# Schematic_MC.net
KiCad netlist of a schematic drawn in Altium Designer
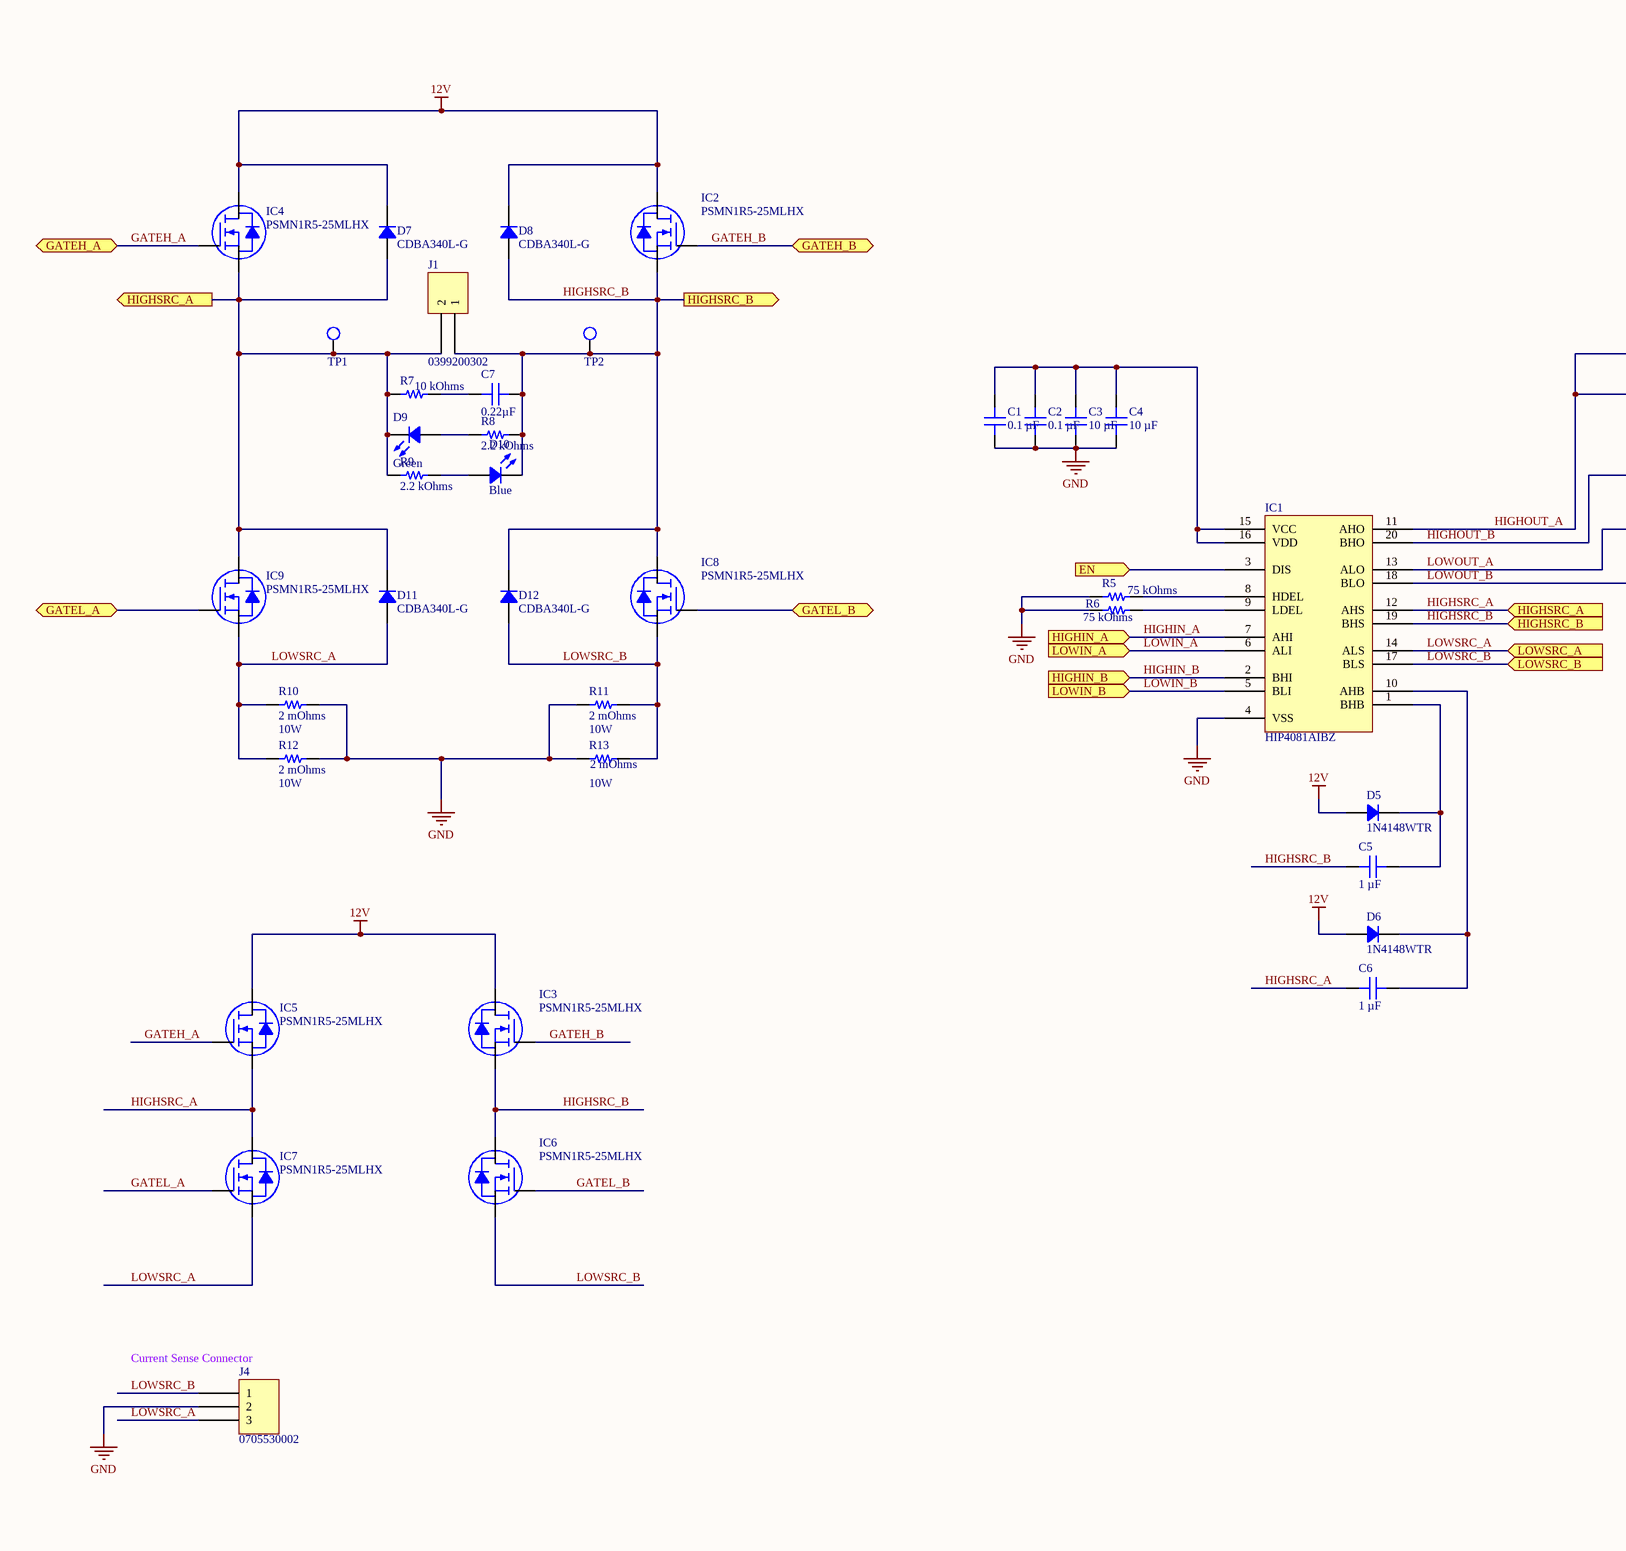
[diagram p0: Schematic_MC.SchDoc, left]
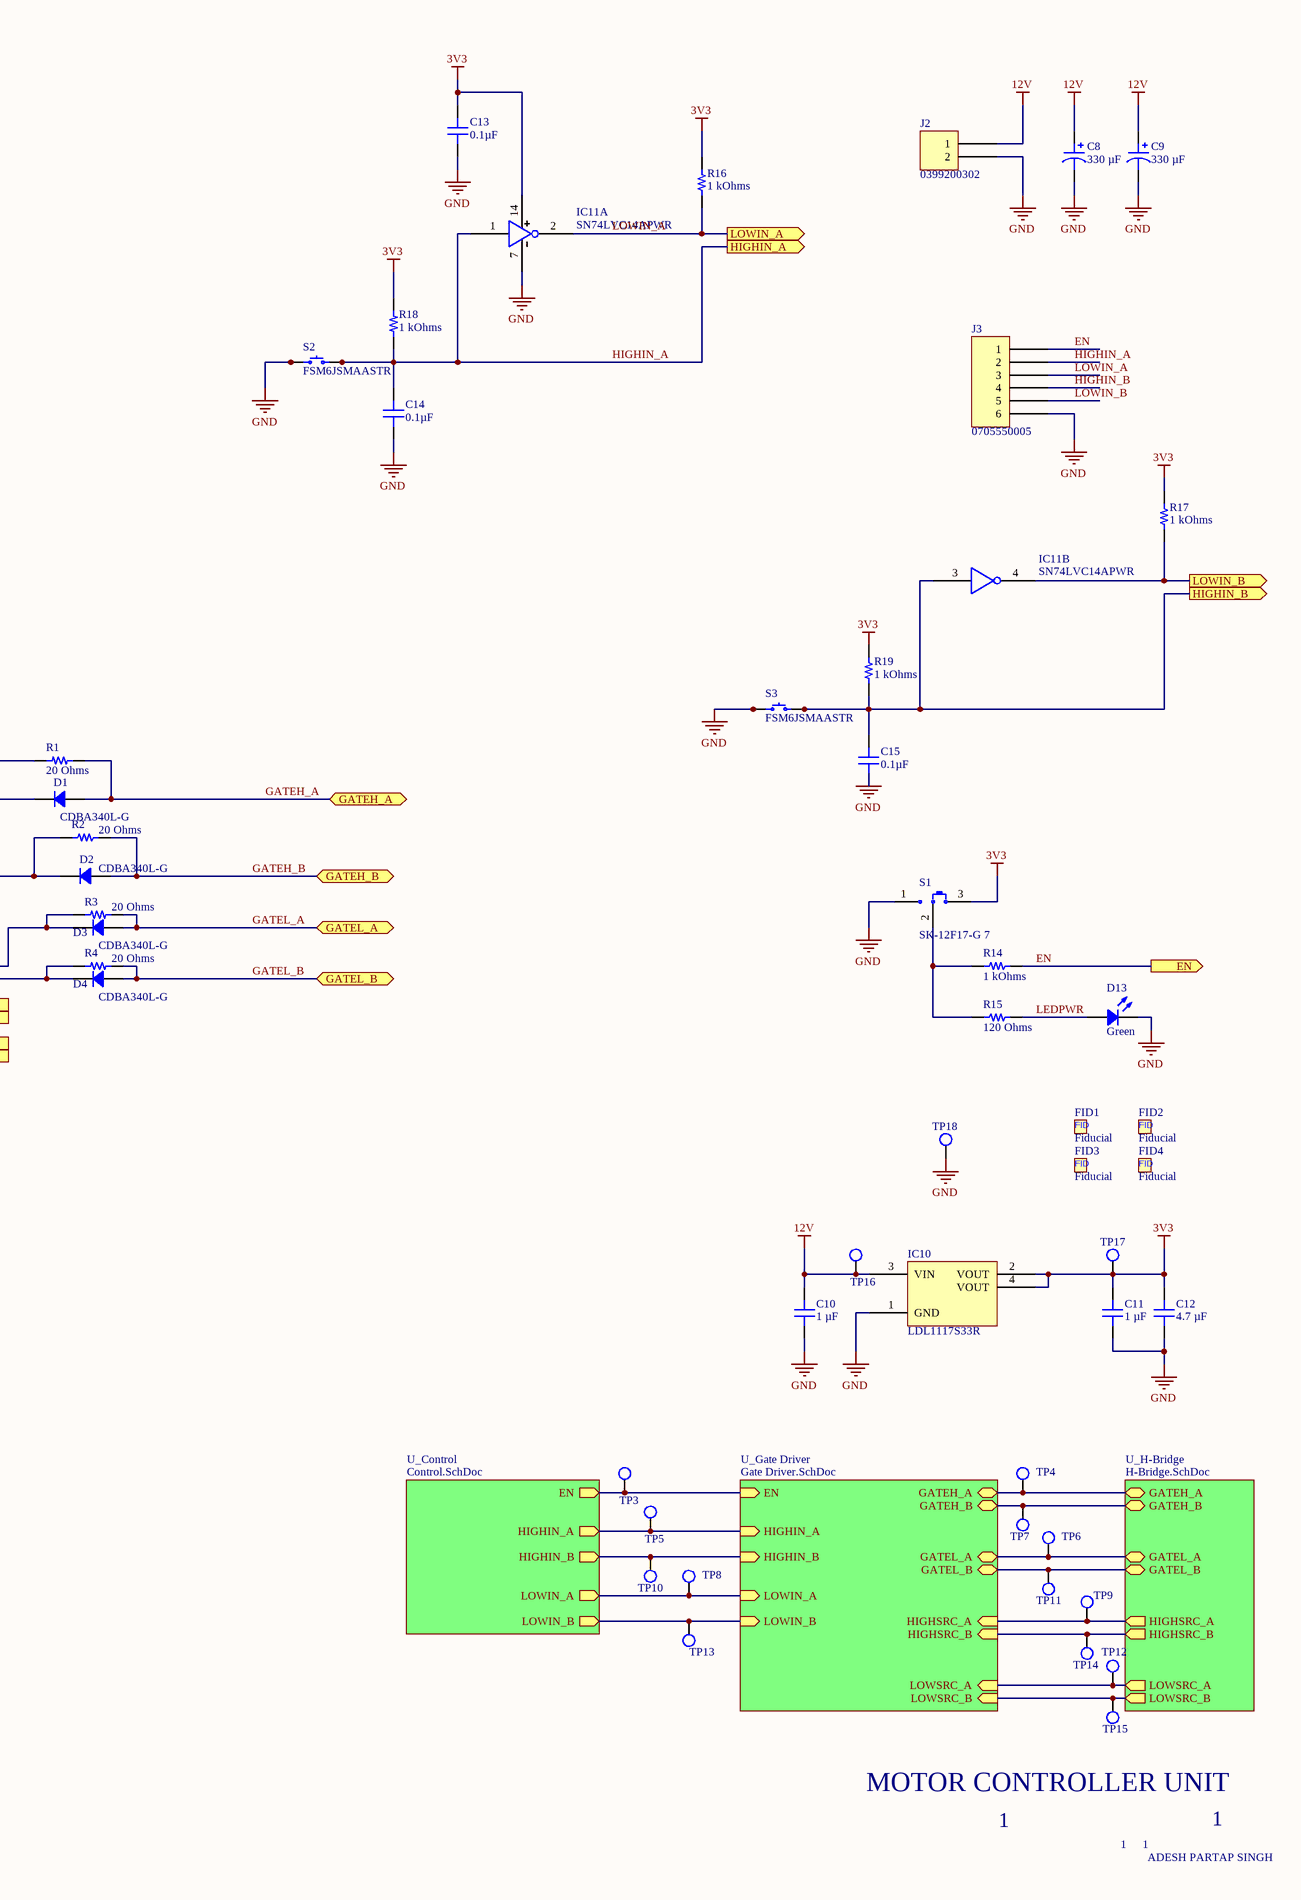
[diagram p1: Schematic_MC.SchDoc, right]

(export (version "E")
  (design (tool "Eeschema 10.0.6"))
  (components
    (comp (ref "C1")
      (value "0.1 µF")
      (footprint "CAP 0603_1608")
      (description "CAP CER 0.1UF 10V X7R 0603")
      (fields (field (name "PART NUMBER") "C0603C104K8RAC7867") (field (name "MANUFACTURER") "KEMET"))
      (libsource (lib "SCH_Lib_MCU") (part "C0603C104K8RAC7867"))
    )
    (comp (ref "C2")
      (value "0.1 µF")
      (footprint "CAP 0603_1608")
      (description "CAP CER 0.1UF 10V X7R 0603")
      (fields (field (name "PART NUMBER") "C0603C104K8RAC7867") (field (name "MANUFACTURER") "KEMET"))
      (libsource (lib "SCH_Lib_MCU") (part "C0603C104K8RAC7867"))
    )
    (comp (ref "C3")
      (value "10 µF")
      (footprint "CAP 1206_3216 - 0.8MM")
      (description "CAP CER 10UF 50V X5R 1206")
      (fields
        (field (name "PART NUMBER") "GRT31CR61H106ME01L")
        (field (name "MANUFACTURER") "Murata Electronics")
      )
      (libsource (lib "SCH_Lib_MCU") (part "GRT31CR61H106ME01L"))
    )
    (comp (ref "C4")
      (value "10 µF")
      (footprint "CAP 1206_3216 - 0.8MM")
      (description "CAP CER 10UF 50V X5R 1206")
      (fields
        (field (name "PART NUMBER") "GRT31CR61H106ME01L")
        (field (name "MANUFACTURER") "Murata Electronics")
      )
      (libsource (lib "SCH_Lib_MCU") (part "GRT31CR61H106ME01L"))
    )
    (comp (ref "C5")
      (value "1 µF")
      (footprint "CAP 0805_2012")
      (description "CAP CER 1UF 50V X7R 0805")
      (fields (field (name "PART NUMBER") "08055C105KAZ2A") (field (name "MANUFACTURER") "KYOCERA AVX"))
      (libsource (lib "SCH_Lib_MCU") (part "08055C105KAZ2A"))
    )
    (comp (ref "C6")
      (value "1 µF")
      (footprint "CAP 0805_2012")
      (description "CAP CER 1UF 50V X7R 0805")
      (fields (field (name "PART NUMBER") "08055C105KAZ2A") (field (name "MANUFACTURER") "KYOCERA AVX"))
      (libsource (lib "SCH_Lib_MCU") (part "08055C105KAZ2A"))
    )
    (comp (ref "C7")
      (value "0.22µF")
      (footprint "CAP 0805_2012")
      (description "CAP CER 0.22UF 50V X7R 0805")
      (fields (field (name "PART NUMBER") "08055C224KAZ2A") (field (name "MANUFACTURER") "AVX Corporation"))
      (libsource (lib "SCH_Lib_MCU") (part "08055C224KAZ2A"))
    )
    (comp (ref "C8")
      (value "330 µF")
      (footprint "CAP TH ALPOLY D10.00mm S5.00mm H13.50mm")
      (description "CAP ALUM POLY 330UF 20% 35V T/H")
      (fields (field (name "PART NUMBER") "337AVG035MGBJ") (field (name "MANUFACTURER") "Illinois Capacitor"))
      (libsource (lib "SCH_Lib_MCU") (part "337AVG035MGBJ"))
    )
    (comp (ref "C9")
      (value "330 µF")
      (footprint "CAP TH ALPOLY D10.00mm S5.00mm H13.50mm")
      (description "CAP ALUM POLY 330UF 20% 35V T/H")
      (fields (field (name "PART NUMBER") "337AVG035MGBJ") (field (name "MANUFACTURER") "Illinois Capacitor"))
      (libsource (lib "SCH_Lib_MCU") (part "337AVG035MGBJ"))
    )
    (comp (ref "C10")
      (value "1 µF")
      (footprint "CAP 0805_2012")
      (description "CAP CER 1UF 50V X7R 0805")
      (fields (field (name "PART NUMBER") "08055C105KAZ2A") (field (name "MANUFACTURER") "KYOCERA AVX"))
      (libsource (lib "SCH_Lib_MCU") (part "08055C105KAZ2A"))
    )
    (comp (ref "C11")
      (value "1 µF")
      (footprint "CAP 0805_2012")
      (description "CAP CER 1UF 50V X7R 0805")
      (fields (field (name "PART NUMBER") "08055C105KAZ2A") (field (name "MANUFACTURER") "KYOCERA AVX"))
      (libsource (lib "SCH_Lib_MCU") (part "08055C105KAZ2A"))
    )
    (comp (ref "C12")
      (value "4.7 µF")
      (footprint "CAP 0805_2012")
      (description "CAP CER 4.7UF 10V X5R 0805")
      (fields (field (name "PART NUMBER") "885012107009") (field (name "MANUFACTURER") "Würth Elektronik"))
      (libsource (lib "SCH_Lib_MCU") (part "885012107009"))
    )
    (comp (ref "C13")
      (value "0.1µF")
      (footprint "CAP 0603_1608")
      (description "CAP CER 0.1UF 50V X7R 0603")
      (fields (field (name "PART NUMBER") "06035C104MAT2A") (field (name "MANUFACTURER") "AVX Corporation"))
      (libsource (lib "SCH_Lib_MCU") (part "06035C104MAT2A"))
    )
    (comp (ref "C14")
      (value "0.1µF")
      (footprint "CAP 0603_1608")
      (description "CAP CER 0.1UF 50V X7R 0603")
      (fields (field (name "PART NUMBER") "06035C104MAT2A") (field (name "MANUFACTURER") "AVX Corporation"))
      (libsource (lib "SCH_Lib_MCU") (part "06035C104MAT2A"))
    )
    (comp (ref "C15")
      (value "0.1µF")
      (footprint "CAP 0603_1608")
      (description "CAP CER 0.1UF 50V X7R 0603")
      (fields (field (name "PART NUMBER") "06035C104MAT2A") (field (name "MANUFACTURER") "AVX Corporation"))
      (libsource (lib "SCH_Lib_MCU") (part "06035C104MAT2A"))
    )
    (comp (ref "D1")
      (value "CDBA340L-G")
      (footprint "DO214AC SMA")
      (description "DIODE SCHOTTKY 40V 3A DO214AC")
      (fields (field (name "MANUFACTURER") "Comchip Technology"))
      (libsource (lib "SCH_Lib_MCU") (part "CDBA340L-G"))
    )
    (comp (ref "D2")
      (value "CDBA340L-G")
      (footprint "DO214AC SMA")
      (description "DIODE SCHOTTKY 40V 3A DO214AC")
      (fields (field (name "MANUFACTURER") "Comchip Technology"))
      (libsource (lib "SCH_Lib_MCU") (part "CDBA340L-G"))
    )
    (comp (ref "D3")
      (value "CDBA340L-G")
      (footprint "DO214AC SMA")
      (description "DIODE SCHOTTKY 40V 3A DO214AC")
      (fields (field (name "MANUFACTURER") "Comchip Technology"))
      (libsource (lib "SCH_Lib_MCU") (part "CDBA340L-G"))
    )
    (comp (ref "D4")
      (value "CDBA340L-G")
      (footprint "DO214AC SMA")
      (description "DIODE SCHOTTKY 40V 3A DO214AC")
      (fields (field (name "MANUFACTURER") "Comchip Technology"))
      (libsource (lib "SCH_Lib_MCU") (part "CDBA340L-G"))
    )
    (comp (ref "D5")
      (value "1N4148WTR")
      (footprint "SOD-123")
      (description "DIODE GEN PURP 75V 250MA SOD123")
      (fields (field (name "MANUFACTURER") "SMC Diode Solutions"))
      (libsource (lib "SCH_Lib_MCU") (part "1N4148WTR"))
    )
    (comp (ref "D6")
      (value "1N4148WTR")
      (footprint "SOD-123")
      (description "DIODE GEN PURP 75V 250MA SOD123")
      (fields (field (name "MANUFACTURER") "SMC Diode Solutions"))
      (libsource (lib "SCH_Lib_MCU") (part "1N4148WTR"))
    )
    (comp (ref "D7")
      (value "CDBA340L-G")
      (footprint "DO214AC SMA")
      (description "DIODE SCHOTTKY 40V 3A DO214AC")
      (fields (field (name "MANUFACTURER") "Comchip Technology"))
      (libsource (lib "SCH_Lib_MCU") (part "CDBA340L-G"))
    )
    (comp (ref "D8")
      (value "CDBA340L-G")
      (footprint "DO214AC SMA")
      (description "DIODE SCHOTTKY 40V 3A DO214AC")
      (fields (field (name "MANUFACTURER") "Comchip Technology"))
      (libsource (lib "SCH_Lib_MCU") (part "CDBA340L-G"))
    )
    (comp (ref "D9")
      (value "Green")
      (footprint "LED 0603_1608 GREEN")
      (description "LED GREEN CLEAR CHIP SMD")
      (fields (field (name "PART NUMBER") "XZMG53W-1") (field (name "MANUFACTURER") "SunLED"))
      (libsource (lib "SCH_Lib_MCU") (part "XZMG53W-1"))
    )
    (comp (ref "D10")
      (value "Blue")
      (footprint "LED 0603_1608 BLUE")
      (description "LED BLUE CLEAR 2SMD")
      (fields
        (field (name "PART NUMBER") "19-213SUBC/S400-A5/S208-2/TR8")
        (field (name "MANUFACTURER") "Everlight Electronics Co Ltd")
      )
      (libsource (lib "SCH_Lib_MCU") (part "19-213SUBC/S400-A5/S208-2/TR8"))
    )
    (comp (ref "D11")
      (value "CDBA340L-G")
      (footprint "DO214AC SMA")
      (description "DIODE SCHOTTKY 40V 3A DO214AC")
      (fields (field (name "MANUFACTURER") "Comchip Technology"))
      (libsource (lib "SCH_Lib_MCU") (part "CDBA340L-G"))
    )
    (comp (ref "D12")
      (value "CDBA340L-G")
      (footprint "DO214AC SMA")
      (description "DIODE SCHOTTKY 40V 3A DO214AC")
      (fields (field (name "MANUFACTURER") "Comchip Technology"))
      (libsource (lib "SCH_Lib_MCU") (part "CDBA340L-G"))
    )
    (comp (ref "D13")
      (value "Green")
      (footprint "LED 0603_1608 GREEN")
      (description "LED GREEN CLEAR CHIP SMD")
      (fields (field (name "PART NUMBER") "XZMG53W-1") (field (name "MANUFACTURER") "SunLED"))
      (libsource (lib "SCH_Lib_MCU") (part "XZMG53W-1"))
    )
    (comp (ref "FID1")
      (value "Fiducial")
      (footprint "Fiducial-1mm")
      (libsource (lib "SCH_Lib_MCU") (part "Fiducial"))
    )
    (comp (ref "FID2")
      (value "Fiducial")
      (footprint "Fiducial-1mm")
      (libsource (lib "SCH_Lib_MCU") (part "Fiducial"))
    )
    (comp (ref "FID3")
      (value "Fiducial")
      (footprint "Fiducial-1mm")
      (libsource (lib "SCH_Lib_MCU") (part "Fiducial"))
    )
    (comp (ref "FID4")
      (value "Fiducial")
      (footprint "Fiducial-1mm")
      (libsource (lib "SCH_Lib_MCU") (part "Fiducial"))
    )
    (comp (ref "IC1")
      (value "HIP4081AIBZ")
      (footprint "INTERSIL SOIC-20 WIDE")
      (description "IC GATE DRVR HALF-BRIDGE 20SOIC")
      (fields (field (name "MANUFACTURER") "Renesas Electronics America Inc."))
      (libsource (lib "SCH_Lib_MCU") (part "HIP4081AIBZ"))
    )
    (comp (ref "IC2")
      (value "PSMN1R5-25MLHX")
      (footprint "NEXPERIA LFPAK33 SOT1210")
      (description "MOSFET N-CH 25V 150A LFPAK33")
      (fields (field (name "MANUFACTURER") "Nexperia USA Inc."))
      (libsource (lib "") (part "PSMN1R5-25MLHX_1"))
    )
    (comp (ref "IC3")
      (value "PSMN1R5-25MLHX")
      (footprint "NEXPERIA LFPAK33 SOT1210")
      (description "MOSFET N-CH 25V 150A LFPAK33")
      (fields (field (name "MANUFACTURER") "Nexperia USA Inc."))
      (libsource (lib "") (part "PSMN1R5-25MLHX_1"))
    )
    (comp (ref "IC4")
      (value "PSMN1R5-25MLHX")
      (footprint "NEXPERIA LFPAK33 SOT1210")
      (description "MOSFET N-CH 25V 150A LFPAK33")
      (fields (field (name "MANUFACTURER") "Nexperia USA Inc."))
      (libsource (lib "SCH_Lib_MCU") (part "PSMN1R5-25MLHX"))
    )
    (comp (ref "IC5")
      (value "PSMN1R5-25MLHX")
      (footprint "NEXPERIA LFPAK33 SOT1210")
      (description "MOSFET N-CH 25V 150A LFPAK33")
      (fields (field (name "MANUFACTURER") "Nexperia USA Inc."))
      (libsource (lib "SCH_Lib_MCU") (part "PSMN1R5-25MLHX"))
    )
    (comp (ref "IC6")
      (value "PSMN1R5-25MLHX")
      (footprint "NEXPERIA LFPAK33 SOT1210")
      (description "MOSFET N-CH 25V 150A LFPAK33")
      (fields (field (name "MANUFACTURER") "Nexperia USA Inc."))
      (libsource (lib "") (part "PSMN1R5-25MLHX_1"))
    )
    (comp (ref "IC7")
      (value "PSMN1R5-25MLHX")
      (footprint "NEXPERIA LFPAK33 SOT1210")
      (description "MOSFET N-CH 25V 150A LFPAK33")
      (fields (field (name "MANUFACTURER") "Nexperia USA Inc."))
      (libsource (lib "SCH_Lib_MCU") (part "PSMN1R5-25MLHX"))
    )
    (comp (ref "IC8")
      (value "PSMN1R5-25MLHX")
      (footprint "NEXPERIA LFPAK33 SOT1210")
      (description "MOSFET N-CH 25V 150A LFPAK33")
      (fields (field (name "MANUFACTURER") "Nexperia USA Inc."))
      (libsource (lib "") (part "PSMN1R5-25MLHX_1"))
    )
    (comp (ref "IC9")
      (value "PSMN1R5-25MLHX")
      (footprint "NEXPERIA LFPAK33 SOT1210")
      (description "MOSFET N-CH 25V 150A LFPAK33")
      (fields (field (name "MANUFACTURER") "Nexperia USA Inc."))
      (libsource (lib "SCH_Lib_MCU") (part "PSMN1R5-25MLHX"))
    )
    (comp (ref "IC10")
      (value "LDL1117S33R")
      (footprint "ST SOT-223")
      (description "IC REG LINEAR 3.3V 1.2A SOT223")
      (fields (field (name "MANUFACTURER") "STMicroelectronics"))
      (libsource (lib "SCH_Lib_MCU") (part "LDL1117S33R"))
    )
    (comp (ref "IC11")
      (value "SN74LVC14APWR")
      (footprint "TI TSSOP-14 PW")
      (description "IC INVERTER 6CH 6-INP 14TSSOP")
      (fields (field (name "MANUFACTURER") "Texas Instruments"))
      (libsource (lib "SCH_Lib_MCU") (part "SN74LVC14APWR"))
    )
    (comp (ref "J1")
      (value "0399200302")
      (footprint "MOLEX 0399200302")
      (description "TERM BLK 2P SIDE ENTRY 15MM PCB")
      (fields (field (name "MANUFACTURER") "Molex") (field (name "VOLTAGE") "600 V"))
      (libsource (lib "") (part "0399200302_1"))
    )
    (comp (ref "J2")
      (value "0399200302")
      (footprint "MOLEX 0399200302")
      (description "TERM BLK 2P SIDE ENTRY 15MM PCB")
      (fields (field (name "MANUFACTURER") "Molex") (field (name "VOLTAGE") "600 V"))
      (libsource (lib "SCH_Lib_MCU") (part "0399200302"))
    )
    (comp (ref "J3")
      (value "0705550005")
      (footprint "MOLEX SDA-70555-6PIN")
      (description "CONN HEADER R/A 6POS 2.54MM")
      (fields (field (name "MANUFACTURER") "Molex"))
      (libsource (lib "SCH_Lib_MCU") (part "0705550005"))
    )
    (comp (ref "J4")
      (value "0705530002")
      (footprint "MOLEX SDA-70553-3PIN")
      (description "CONN HEADER R/A 3POS 2.54MM")
      (fields (field (name "MANUFACTURER") "Molex"))
      (libsource (lib "SCH_Lib_MCU") (part "0705530002"))
    )
    (comp (ref "R1")
      (value "20 Ohms")
      (footprint "RES 0805_2012")
      (description "RES SMD 20 OHM 5% 1/8W 0805")
      (fields
        (field (name "PART NUMBER") "ERJ-6GEYJ200V")
        (field (name "MANUFACTURER") "Panasonic Electronic Components")
      )
      (libsource (lib "SCH_Lib_MCU") (part "ERJ-6GEYJ200V"))
    )
    (comp (ref "R2")
      (value "20 Ohms")
      (footprint "RES 0805_2012")
      (description "RES SMD 20 OHM 5% 1/8W 0805")
      (fields
        (field (name "PART NUMBER") "ERJ-6GEYJ200V")
        (field (name "MANUFACTURER") "Panasonic Electronic Components")
      )
      (libsource (lib "SCH_Lib_MCU") (part "ERJ-6GEYJ200V"))
    )
    (comp (ref "R3")
      (value "20 Ohms")
      (footprint "RES 0805_2012")
      (description "RES SMD 20 OHM 5% 1/8W 0805")
      (fields
        (field (name "PART NUMBER") "ERJ-6GEYJ200V")
        (field (name "MANUFACTURER") "Panasonic Electronic Components")
      )
      (libsource (lib "SCH_Lib_MCU") (part "ERJ-6GEYJ200V"))
    )
    (comp (ref "R4")
      (value "20 Ohms")
      (footprint "RES 0805_2012")
      (description "RES SMD 20 OHM 5% 1/8W 0805")
      (fields
        (field (name "PART NUMBER") "ERJ-6GEYJ200V")
        (field (name "MANUFACTURER") "Panasonic Electronic Components")
      )
      (libsource (lib "SCH_Lib_MCU") (part "ERJ-6GEYJ200V"))
    )
    (comp (ref "R5")
      (value "75 kOhms")
      (footprint "RES 0603_1608")
      (description "RES 75K OHM 1% 1/10W 0603")
      (fields (field (name "PART NUMBER") "CRCW060375K0FKEAC") (field (name "MANUFACTURER") "Vishay Dale"))
      (libsource (lib "SCH_Lib_MCU") (part "CRCW060375K0FKEAC"))
    )
    (comp (ref "R6")
      (value "75 kOhms")
      (footprint "RES 0603_1608")
      (description "RES 75K OHM 1% 1/10W 0603")
      (fields (field (name "PART NUMBER") "CRCW060375K0FKEAC") (field (name "MANUFACTURER") "Vishay Dale"))
      (libsource (lib "SCH_Lib_MCU") (part "CRCW060375K0FKEAC"))
    )
    (comp (ref "R7")
      (value "10 kOhms")
      (footprint "RES 0805_2012")
      (description "RES SMD 10K OHM 5% 1/2W 0805")
      (fields
        (field (name "PART NUMBER") "ERJ-P06J103V")
        (field (name "MANUFACTURER") "Panasonic Electronic Components")
      )
      (libsource (lib "SCH_Lib_MCU") (part "ERJ-P06J103V"))
    )
    (comp (ref "R8")
      (value "2.2 kOhms")
      (footprint "RES 0603_1608")
      (description "RES SMD 2.2K OHM 5% 1/4W 0603")
      (fields
        (field (name "PART NUMBER") "ERJ-PA3J222V")
        (field (name "MANUFACTURER") "Panasonic Electronic Components")
      )
      (libsource (lib "SCH_Lib_MCU") (part "ERJ-PA3J222V"))
    )
    (comp (ref "R9")
      (value "2.2 kOhms")
      (footprint "RES 0603_1608")
      (description "RES SMD 2.2K OHM 5% 1/4W 0603")
      (fields
        (field (name "PART NUMBER") "ERJ-PA3J222V")
        (field (name "MANUFACTURER") "Panasonic Electronic Components")
      )
      (libsource (lib "SCH_Lib_MCU") (part "ERJ-PA3J222V"))
    )
    (comp (ref "R10")
      (value "2 mOhms")
      (footprint "VISHAY WSHP2818")
      (description "RES 0.002 OHM 1% 10W 2818")
      (fields
        (field (name "PART NUMBER") "WSHP28182L000FEA")
        (field (name "MANUFACTURER") "Vishay Dale")
        (field (name "POWER (WATTS)") "10W")
      )
      (libsource (lib "SCH_Lib_MCU") (part "WSHP28182L000FEA"))
    )
    (comp (ref "R11")
      (value "2 mOhms")
      (footprint "VISHAY WSHP2818")
      (description "RES 0.002 OHM 1% 10W 2818")
      (fields
        (field (name "PART NUMBER") "WSHP28182L000FEA")
        (field (name "MANUFACTURER") "Vishay Dale")
        (field (name "POWER (WATTS)") "10W")
      )
      (libsource (lib "SCH_Lib_MCU") (part "WSHP28182L000FEA"))
    )
    (comp (ref "R12")
      (value "2 mOhms")
      (footprint "VISHAY WSHP2818")
      (description "RES 0.002 OHM 1% 10W 2818")
      (fields
        (field (name "PART NUMBER") "WSHP28182L000FEA")
        (field (name "MANUFACTURER") "Vishay Dale")
        (field (name "POWER (WATTS)") "10W")
      )
      (libsource (lib "SCH_Lib_MCU") (part "WSHP28182L000FEA"))
    )
    (comp (ref "R13")
      (value "2 mOhms")
      (footprint "VISHAY WSHP2818")
      (description "RES 0.002 OHM 1% 10W 2818")
      (fields
        (field (name "PART NUMBER") "WSHP28182L000FEA")
        (field (name "MANUFACTURER") "Vishay Dale")
        (field (name "POWER (WATTS)") "10W")
      )
      (libsource (lib "SCH_Lib_MCU") (part "WSHP28182L000FEA"))
    )
    (comp (ref "R14")
      (value "1 kOhms")
      (footprint "RES 0603_1608")
      (description "RES SMD 1K OHM 5% 1/4W 0603")
      (fields
        (field (name "PART NUMBER") "ERJ-PA3J102V")
        (field (name "MANUFACTURER") "Panasonic Electronic Components")
      )
      (libsource (lib "SCH_Lib_MCU") (part "ERJ-PA3J102V"))
    )
    (comp (ref "R15")
      (value "120 Ohms")
      (footprint "RES 0603_1608")
      (description "RES SMD 120 OHM 5% 1/4W 0603")
      (fields
        (field (name "PART NUMBER") "ERJ-PA3J121V")
        (field (name "MANUFACTURER") "Panasonic Electronic Components")
      )
      (libsource (lib "SCH_Lib_MCU") (part "ERJ-PA3J121V"))
    )
    (comp (ref "R16")
      (value "1 kOhms")
      (footprint "RES 0603_1608")
      (description "RES SMD 1K OHM 5% 1/4W 0603")
      (fields
        (field (name "PART NUMBER") "ERJ-PA3J102V")
        (field (name "MANUFACTURER") "Panasonic Electronic Components")
      )
      (libsource (lib "SCH_Lib_MCU") (part "ERJ-PA3J102V"))
    )
    (comp (ref "R17")
      (value "1 kOhms")
      (footprint "RES 0603_1608")
      (description "RES SMD 1K OHM 5% 1/4W 0603")
      (fields
        (field (name "PART NUMBER") "ERJ-PA3J102V")
        (field (name "MANUFACTURER") "Panasonic Electronic Components")
      )
      (libsource (lib "SCH_Lib_MCU") (part "ERJ-PA3J102V"))
    )
    (comp (ref "R18")
      (value "1 kOhms")
      (footprint "RES 0603_1608")
      (description "RES SMD 1K OHM 5% 1/4W 0603")
      (fields
        (field (name "PART NUMBER") "ERJ-PA3J102V")
        (field (name "MANUFACTURER") "Panasonic Electronic Components")
      )
      (libsource (lib "SCH_Lib_MCU") (part "ERJ-PA3J102V"))
    )
    (comp (ref "R19")
      (value "1 kOhms")
      (footprint "RES 0603_1608")
      (description "RES SMD 1K OHM 5% 1/4W 0603")
      (fields
        (field (name "PART NUMBER") "ERJ-PA3J102V")
        (field (name "MANUFACTURER") "Panasonic Electronic Components")
      )
      (libsource (lib "SCH_Lib_MCU") (part "ERJ-PA3J102V"))
    )
    (comp (ref "S1")
      (value "SK-12F17-G 7")
      (footprint "C&K SK-12F17-G 7")
      (description "SWITCH SLIDE SPDT 300MA 30V")
      (fields (field (name "MANUFACTURER") "C&K"))
      (libsource (lib "SCH_Lib_MCU") (part "SK-12F17-G 7"))
    )
    (comp (ref "S2")
      (value "FSM6JSMAASTR")
      (footprint "TE FSM6JSMA")
      (description "SWITCH TACTILE SPST-NO 0.05A 24V")
      (fields (field (name "MANUFACTURER") "TE Connectivity ALCOSWITCH Switches"))
      (libsource (lib "SCH_Lib_MCU") (part "FSM6JSMAASTR"))
    )
    (comp (ref "S3")
      (value "FSM6JSMAASTR")
      (footprint "TE FSM6JSMA")
      (description "SWITCH TACTILE SPST-NO 0.05A 24V")
      (fields (field (name "MANUFACTURER") "TE Connectivity ALCOSWITCH Switches"))
      (libsource (lib "SCH_Lib_MCU") (part "FSM6JSMAASTR"))
    )
    (comp (ref "TP1")
      (value "Test Point")
      (footprint "TestPoint-1.5mm")
      (libsource (lib "SCH_Lib_MCU") (part "Test Point"))
    )
    (comp (ref "TP2")
      (value "Test Point")
      (footprint "TestPoint-1.5mm")
      (libsource (lib "SCH_Lib_MCU") (part "Test Point"))
    )
    (comp (ref "TP3")
      (value "Test Point")
      (footprint "TestPoint-1.5mm")
      (libsource (lib "SCH_Lib_MCU") (part "Test Point"))
    )
    (comp (ref "TP4")
      (value "Test Point")
      (footprint "TestPoint-1.5mm")
      (libsource (lib "SCH_Lib_MCU") (part "Test Point"))
    )
    (comp (ref "TP5")
      (value "Test Point")
      (footprint "TestPoint-1.5mm")
      (libsource (lib "SCH_Lib_MCU") (part "Test Point"))
    )
    (comp (ref "TP6")
      (value "Test Point")
      (footprint "TestPoint-1.5mm")
      (libsource (lib "SCH_Lib_MCU") (part "Test Point"))
    )
    (comp (ref "TP7")
      (value "Test Point")
      (footprint "TestPoint-1.5mm")
      (libsource (lib "SCH_Lib_MCU") (part "Test Point"))
    )
    (comp (ref "TP8")
      (value "Test Point")
      (footprint "TestPoint-1.5mm")
      (libsource (lib "SCH_Lib_MCU") (part "Test Point"))
    )
    (comp (ref "TP9")
      (value "Test Point")
      (footprint "TestPoint-1.5mm")
      (libsource (lib "SCH_Lib_MCU") (part "Test Point"))
    )
    (comp (ref "TP10")
      (value "Test Point")
      (footprint "TestPoint-1.5mm")
      (libsource (lib "SCH_Lib_MCU") (part "Test Point"))
    )
    (comp (ref "TP11")
      (value "Test Point")
      (footprint "TestPoint-1.5mm")
      (libsource (lib "SCH_Lib_MCU") (part "Test Point"))
    )
    (comp (ref "TP12")
      (value "Test Point")
      (footprint "TestPoint-1.5mm")
      (libsource (lib "SCH_Lib_MCU") (part "Test Point"))
    )
    (comp (ref "TP13")
      (value "Test Point")
      (footprint "TestPoint-1.5mm")
      (libsource (lib "SCH_Lib_MCU") (part "Test Point"))
    )
    (comp (ref "TP14")
      (value "Test Point")
      (footprint "TestPoint-1.5mm")
      (libsource (lib "SCH_Lib_MCU") (part "Test Point"))
    )
    (comp (ref "TP15")
      (value "Test Point")
      (footprint "TestPoint-1.5mm")
      (libsource (lib "SCH_Lib_MCU") (part "Test Point"))
    )
    (comp (ref "TP16")
      (value "Test Point")
      (footprint "TestPoint-1.5mm")
      (libsource (lib "SCH_Lib_MCU") (part "Test Point"))
    )
    (comp (ref "TP17")
      (value "Test Point")
      (footprint "TestPoint-1.5mm")
      (libsource (lib "SCH_Lib_MCU") (part "Test Point"))
    )
    (comp (ref "TP18")
      (value "Test Point")
      (footprint "TestPoint-1.5mm")
      (libsource (lib "SCH_Lib_MCU") (part "Test Point"))
    )
  )
  (nets
    (net (code "1") (name "/EN") (class "Default")
      (node (ref "IC1") (pin "3") (pinfunction "DIS_3") (pintype "passive"))
      (node (ref "J3") (pin "1") (pinfunction "1_1") (pintype "passive"))
      (node (ref "R14") (pin "2") (pinfunction "2_2") (pintype "passive"))
    )
    (net (code "2") (name "/EN_1") (class "Default")
      (node (ref "TP3") (pin "1") (pinfunction "TP_1") (pintype "passive"))
    )
    (net (code "3") (name "/GATEH_A") (class "Default")
      (node (ref "D1") (pin "1") (pinfunction "1_1") (pintype "passive"))
      (node (ref "IC4") (pin "G") (pinfunction "G_G") (pintype "passive"))
      (node (ref "IC5") (pin "G") (pinfunction "G_G") (pintype "passive"))
      (node (ref "R1") (pin "2") (pinfunction "2_2") (pintype "passive"))
    )
    (net (code "4") (name "/GATEH_A_1") (class "Default")
      (node (ref "TP4") (pin "1") (pinfunction "TP_1") (pintype "passive"))
    )
    (net (code "5") (name "/GATEH_B") (class "Default")
      (node (ref "D2") (pin "1") (pinfunction "1_1") (pintype "passive"))
      (node (ref "IC2") (pin "G") (pinfunction "G_G") (pintype "passive"))
      (node (ref "IC3") (pin "G") (pinfunction "G_G") (pintype "passive"))
      (node (ref "R2") (pin "2") (pinfunction "2_2") (pintype "passive"))
    )
    (net (code "6") (name "/GATEH_B_1") (class "Default")
      (node (ref "TP7") (pin "1") (pinfunction "TP_1") (pintype "passive"))
    )
    (net (code "7") (name "/GATEL_A") (class "Default")
      (node (ref "D3") (pin "1") (pinfunction "1_1") (pintype "passive"))
      (node (ref "IC7") (pin "G") (pinfunction "G_G") (pintype "passive"))
      (node (ref "IC9") (pin "G") (pinfunction "G_G") (pintype "passive"))
      (node (ref "R3") (pin "2") (pinfunction "2_2") (pintype "passive"))
    )
    (net (code "8") (name "/GATEL_A_1") (class "Default")
      (node (ref "TP6") (pin "1") (pinfunction "TP_1") (pintype "passive"))
    )
    (net (code "9") (name "/GATEL_B") (class "Default")
      (node (ref "D4") (pin "1") (pinfunction "1_1") (pintype "passive"))
      (node (ref "IC6") (pin "G") (pinfunction "G_G") (pintype "passive"))
      (node (ref "IC8") (pin "G") (pinfunction "G_G") (pintype "passive"))
      (node (ref "R4") (pin "2") (pinfunction "2_2") (pintype "passive"))
    )
    (net (code "10") (name "/GATEL_B_1") (class "Default")
      (node (ref "TP11") (pin "1") (pinfunction "TP_1") (pintype "passive"))
    )
    (net (code "11") (name "/HIGHIN_A") (class "Default")
      (node (ref "C14") (pin "2") (pinfunction "2_2") (pintype "passive"))
      (node (ref "IC1") (pin "7") (pinfunction "AHI_7") (pintype "passive"))
      (node (ref "IC11") (pin "1") (pinfunction "1A_1") (pintype "passive"))
      (node (ref "J3") (pin "2") (pinfunction "2_2") (pintype "passive"))
      (node (ref "R18") (pin "1") (pinfunction "1_1") (pintype "passive"))
      (node (ref "S2") (pin "3") (pinfunction "3_3") (pintype "passive"))
      (node (ref "S2") (pin "4") (pinfunction "4_4") (pintype "passive"))
    )
    (net (code "12") (name "/HIGHIN_A_1") (class "Default")
      (node (ref "TP5") (pin "1") (pinfunction "TP_1") (pintype "passive"))
    )
    (net (code "13") (name "/HIGHIN_B") (class "Default")
      (node (ref "C15") (pin "2") (pinfunction "2_2") (pintype "passive"))
      (node (ref "IC1") (pin "2") (pinfunction "BHI_2") (pintype "passive"))
      (node (ref "IC11") (pin "3") (pinfunction "2A_3") (pintype "passive"))
      (node (ref "J3") (pin "4") (pinfunction "4_4") (pintype "passive"))
      (node (ref "R19") (pin "1") (pinfunction "1_1") (pintype "passive"))
      (node (ref "S3") (pin "3") (pinfunction "3_3") (pintype "passive"))
      (node (ref "S3") (pin "4") (pinfunction "4_4") (pintype "passive"))
    )
    (net (code "14") (name "/HIGHIN_B_1") (class "Default")
      (node (ref "TP10") (pin "1") (pinfunction "TP_1") (pintype "passive"))
    )
    (net (code "15") (name "/HIGHOUT_A") (class "Default")
      (node (ref "D1") (pin "2") (pinfunction "2_2") (pintype "passive"))
      (node (ref "IC1") (pin "11") (pinfunction "AHO_11") (pintype "passive"))
      (node (ref "R1") (pin "1") (pinfunction "1_1") (pintype "passive"))
    )
    (net (code "16") (name "/HIGHOUT_B") (class "Default")
      (node (ref "D2") (pin "2") (pinfunction "2_2") (pintype "passive"))
      (node (ref "IC1") (pin "20") (pinfunction "BHO_20") (pintype "passive"))
      (node (ref "R2") (pin "1") (pinfunction "1_1") (pintype "passive"))
    )
    (net (code "17") (name "/HIGHSRC_A") (class "Default")
      (node (ref "C6") (pin "1") (pinfunction "1_1") (pintype "passive"))
      (node (ref "D11") (pin "2") (pinfunction "2_2") (pintype "passive"))
      (node (ref "D7") (pin "1") (pinfunction "1_1") (pintype "passive"))
      (node (ref "D9") (pin "2") (pinfunction "2_2") (pintype "passive"))
      (node (ref "IC1") (pin "12") (pinfunction "AHS_12") (pintype "passive"))
      (node (ref "IC4") (pin "S") (pinfunction "S_S") (pintype "passive"))
      (node (ref "IC5") (pin "S") (pinfunction "S_S") (pintype "passive"))
      (node (ref "IC7") (pin "D") (pinfunction "D_D") (pintype "passive"))
      (node (ref "IC9") (pin "D") (pinfunction "D_D") (pintype "passive"))
      (node (ref "J1") (pin "2") (pinfunction "2_2") (pintype "passive"))
      (node (ref "R7") (pin "1") (pinfunction "1_1") (pintype "passive"))
      (node (ref "R9") (pin "1") (pinfunction "1_1") (pintype "passive"))
      (node (ref "TP1") (pin "1") (pinfunction "TP_1") (pintype "passive"))
    )
    (net (code "18") (name "/HIGHSRC_A_1") (class "Default")
      (node (ref "TP9") (pin "1") (pinfunction "TP_1") (pintype "passive"))
    )
    (net (code "19") (name "/HIGHSRC_B") (class "Default")
      (node (ref "C5") (pin "1") (pinfunction "1_1") (pintype "passive"))
      (node (ref "C7") (pin "2") (pinfunction "2_2") (pintype "passive"))
      (node (ref "D10") (pin "2") (pinfunction "2_2") (pintype "passive"))
      (node (ref "D12") (pin "2") (pinfunction "2_2") (pintype "passive"))
      (node (ref "D8") (pin "1") (pinfunction "1_1") (pintype "passive"))
      (node (ref "IC1") (pin "19") (pinfunction "BHS_19") (pintype "passive"))
      (node (ref "IC2") (pin "S") (pinfunction "S_S") (pintype "passive"))
      (node (ref "IC3") (pin "S") (pinfunction "S_S") (pintype "passive"))
      (node (ref "IC6") (pin "D") (pinfunction "D_D") (pintype "passive"))
      (node (ref "IC8") (pin "D") (pinfunction "D_D") (pintype "passive"))
      (node (ref "J1") (pin "1") (pinfunction "1_1") (pintype "passive"))
      (node (ref "R8") (pin "2") (pinfunction "2_2") (pintype "passive"))
      (node (ref "TP2") (pin "1") (pinfunction "TP_1") (pintype "passive"))
    )
    (net (code "20") (name "/HIGHSRC_B_1") (class "Default")
      (node (ref "TP14") (pin "1") (pinfunction "TP_1") (pintype "passive"))
    )
    (net (code "21") (name "/LEDPWR") (class "Default")
      (node (ref "D13") (pin "1") (pinfunction "1_1") (pintype "passive"))
      (node (ref "R15") (pin "2") (pinfunction "2_2") (pintype "passive"))
    )
    (net (code "22") (name "/LOWIN_A") (class "Default")
      (node (ref "IC1") (pin "6") (pinfunction "ALI_6") (pintype "passive"))
      (node (ref "IC11") (pin "2") (pinfunction "1Y_2") (pintype "passive"))
      (node (ref "J3") (pin "3") (pinfunction "3_3") (pintype "passive"))
      (node (ref "R16") (pin "1") (pinfunction "1_1") (pintype "passive"))
    )
    (net (code "23") (name "/LOWIN_A_1") (class "Default")
      (node (ref "TP8") (pin "1") (pinfunction "TP_1") (pintype "passive"))
    )
    (net (code "24") (name "/LOWIN_B") (class "Default")
      (node (ref "IC1") (pin "5") (pinfunction "BLI_5") (pintype "passive"))
      (node (ref "IC11") (pin "4") (pinfunction "2Y_4") (pintype "passive"))
      (node (ref "J3") (pin "5") (pinfunction "5_5") (pintype "passive"))
      (node (ref "R17") (pin "1") (pinfunction "1_1") (pintype "passive"))
    )
    (net (code "25") (name "/LOWIN_B_1") (class "Default")
      (node (ref "TP13") (pin "1") (pinfunction "TP_1") (pintype "passive"))
    )
    (net (code "26") (name "/LOWOUT_A") (class "Default")
      (node (ref "D3") (pin "2") (pinfunction "2_2") (pintype "passive"))
      (node (ref "IC1") (pin "13") (pinfunction "ALO_13") (pintype "passive"))
      (node (ref "R3") (pin "1") (pinfunction "1_1") (pintype "passive"))
    )
    (net (code "27") (name "/LOWOUT_B") (class "Default")
      (node (ref "D4") (pin "2") (pinfunction "2_2") (pintype "passive"))
      (node (ref "IC1") (pin "18") (pinfunction "BLO_18") (pintype "passive"))
      (node (ref "R4") (pin "1") (pinfunction "1_1") (pintype "passive"))
    )
    (net (code "28") (name "/LOWSRC_A") (class "Default")
      (node (ref "D11") (pin "1") (pinfunction "1_1") (pintype "passive"))
      (node (ref "IC1") (pin "14") (pinfunction "ALS_14") (pintype "passive"))
      (node (ref "IC7") (pin "S") (pinfunction "S_S") (pintype "passive"))
      (node (ref "IC9") (pin "S") (pinfunction "S_S") (pintype "passive"))
      (node (ref "J4") (pin "3") (pinfunction "3_3") (pintype "passive"))
      (node (ref "R10") (pin "1") (pinfunction "1_1") (pintype "passive"))
      (node (ref "R12") (pin "1") (pinfunction "1_1") (pintype "passive"))
    )
    (net (code "29") (name "/LOWSRC_A_1") (class "Default")
      (node (ref "TP12") (pin "1") (pinfunction "TP_1") (pintype "passive"))
    )
    (net (code "30") (name "/LOWSRC_B") (class "Default")
      (node (ref "D12") (pin "1") (pinfunction "1_1") (pintype "passive"))
      (node (ref "IC1") (pin "17") (pinfunction "BLS_17") (pintype "passive"))
      (node (ref "IC6") (pin "S") (pinfunction "S_S") (pintype "passive"))
      (node (ref "IC8") (pin "S") (pinfunction "S_S") (pintype "passive"))
      (node (ref "J4") (pin "1") (pinfunction "1_1") (pintype "passive"))
      (node (ref "R11") (pin "2") (pinfunction "2_2") (pintype "passive"))
      (node (ref "R13") (pin "2") (pinfunction "2_2") (pintype "passive"))
    )
    (net (code "31") (name "/LOWSRC_B_1") (class "Default")
      (node (ref "TP15") (pin "1") (pinfunction "TP_1") (pintype "passive"))
    )
    (net (code "32") (name "3V3") (class "Default")
      (node (ref "C11") (pin "2") (pinfunction "2_2") (pintype "passive"))
      (node (ref "C12") (pin "2") (pinfunction "2_2") (pintype "passive"))
      (node (ref "C13") (pin "2") (pinfunction "2_2") (pintype "passive"))
      (node (ref "IC10") (pin "2") (pinfunction "VOUT_2") (pintype "passive"))
      (node (ref "IC10") (pin "4") (pinfunction "VOUT_4") (pintype "passive"))
      (node (ref "IC11") (pin "14") (pinfunction "VCC_14") (pintype "passive"))
      (node (ref "R16") (pin "2") (pinfunction "2_2") (pintype "passive"))
      (node (ref "R17") (pin "2") (pinfunction "2_2") (pintype "passive"))
      (node (ref "R18") (pin "2") (pinfunction "2_2") (pintype "passive"))
      (node (ref "R19") (pin "2") (pinfunction "2_2") (pintype "passive"))
      (node (ref "S1") (pin "3") (pinfunction "3_3") (pintype "passive"))
      (node (ref "TP17") (pin "1") (pinfunction "TP_1") (pintype "passive"))
    )
    (net (code "33") (name "12V") (class "Default")
      (node (ref "C10") (pin "2") (pinfunction "2_2") (pintype "passive"))
      (node (ref "C8") (pin "1") (pinfunction "1_1") (pintype "passive"))
      (node (ref "C9") (pin "1") (pinfunction "1_1") (pintype "passive"))
      (node (ref "D5") (pin "1") (pinfunction "1_1") (pintype "passive"))
      (node (ref "D6") (pin "1") (pinfunction "1_1") (pintype "passive"))
      (node (ref "D7") (pin "2") (pinfunction "2_2") (pintype "passive"))
      (node (ref "D8") (pin "2") (pinfunction "2_2") (pintype "passive"))
      (node (ref "IC10") (pin "3") (pinfunction "VIN_3") (pintype "passive"))
      (node (ref "IC2") (pin "D") (pinfunction "D_D") (pintype "passive"))
      (node (ref "IC3") (pin "D") (pinfunction "D_D") (pintype "passive"))
      (node (ref "IC4") (pin "D") (pinfunction "D_D") (pintype "passive"))
      (node (ref "IC5") (pin "D") (pinfunction "D_D") (pintype "passive"))
      (node (ref "J2") (pin "1") (pinfunction "1_1") (pintype "passive"))
      (node (ref "TP16") (pin "1") (pinfunction "TP_1") (pintype "passive"))
    )
    (net (code "34") (name "GND") (class "Default")
      (node (ref "C1") (pin "1") (pinfunction "1_1") (pintype "passive"))
      (node (ref "C10") (pin "1") (pinfunction "1_1") (pintype "passive"))
      (node (ref "C11") (pin "1") (pinfunction "1_1") (pintype "passive"))
      (node (ref "C12") (pin "1") (pinfunction "1_1") (pintype "passive"))
      (node (ref "C13") (pin "1") (pinfunction "1_1") (pintype "passive"))
      (node (ref "C14") (pin "1") (pinfunction "1_1") (pintype "passive"))
      (node (ref "C15") (pin "1") (pinfunction "1_1") (pintype "passive"))
      (node (ref "C2") (pin "1") (pinfunction "1_1") (pintype "passive"))
      (node (ref "C3") (pin "1") (pinfunction "1_1") (pintype "passive"))
      (node (ref "C4") (pin "1") (pinfunction "1_1") (pintype "passive"))
      (node (ref "C8") (pin "2") (pinfunction "2_2") (pintype "passive"))
      (node (ref "C9") (pin "2") (pinfunction "2_2") (pintype "passive"))
      (node (ref "D13") (pin "2") (pinfunction "2_2") (pintype "passive"))
      (node (ref "IC1") (pin "4") (pinfunction "VSS_4") (pintype "passive"))
      (node (ref "IC10") (pin "1") (pinfunction "GND_1") (pintype "passive"))
      (node (ref "IC11") (pin "7") (pinfunction "GND_7") (pintype "passive"))
      (node (ref "J2") (pin "2") (pinfunction "2_2") (pintype "passive"))
      (node (ref "J3") (pin "6") (pinfunction "6_6") (pintype "passive"))
      (node (ref "J4") (pin "2") (pinfunction "2_2") (pintype "passive"))
      (node (ref "R10") (pin "2") (pinfunction "2_2") (pintype "passive"))
      (node (ref "R11") (pin "1") (pinfunction "1_1") (pintype "passive"))
      (node (ref "R12") (pin "2") (pinfunction "2_2") (pintype "passive"))
      (node (ref "R13") (pin "1") (pinfunction "1_1") (pintype "passive"))
      (node (ref "R5") (pin "1") (pinfunction "1_1") (pintype "passive"))
      (node (ref "R6") (pin "1") (pinfunction "1_1") (pintype "passive"))
      (node (ref "S1") (pin "1") (pinfunction "1_1") (pintype "passive"))
      (node (ref "S2") (pin "1") (pinfunction "1_1") (pintype "passive"))
      (node (ref "S2") (pin "2") (pinfunction "2_2") (pintype "passive"))
      (node (ref "S3") (pin "1") (pinfunction "1_1") (pintype "passive"))
      (node (ref "S3") (pin "2") (pinfunction "2_2") (pintype "passive"))
      (node (ref "TP18") (pin "1") (pinfunction "TP_1") (pintype "passive"))
    )
    (net (code "35") (name "Net-(C7-Pad1)") (class "Default")
      (node (ref "C7") (pin "1") (pinfunction "1_1") (pintype "passive"))
      (node (ref "R7") (pin "2") (pinfunction "2_2") (pintype "passive"))
    )
    (net (code "36") (name "Net-(D9-Pad1)") (class "Default")
      (node (ref "D9") (pin "1") (pinfunction "1_1") (pintype "passive"))
      (node (ref "R8") (pin "1") (pinfunction "1_1") (pintype "passive"))
    )
    (net (code "37") (name "Net-(D10-Pad1)") (class "Default")
      (node (ref "D10") (pin "1") (pinfunction "1_1") (pintype "passive"))
      (node (ref "R9") (pin "2") (pinfunction "2_2") (pintype "passive"))
    )
    (net (code "38") (name "Net-(IC1-AHB)") (class "Default")
      (node (ref "C6") (pin "2") (pinfunction "2_2") (pintype "passive"))
      (node (ref "D6") (pin "2") (pinfunction "2_2") (pintype "passive"))
      (node (ref "IC1") (pin "10") (pinfunction "AHB_10") (pintype "passive"))
    )
    (net (code "39") (name "Net-(IC1-BHB)") (class "Default")
      (node (ref "C5") (pin "2") (pinfunction "2_2") (pintype "passive"))
      (node (ref "D5") (pin "2") (pinfunction "2_2") (pintype "passive"))
      (node (ref "IC1") (pin "1") (pinfunction "BHB_1") (pintype "passive"))
    )
    (net (code "40") (name "Net-(IC1-HDEL)") (class "Default")
      (node (ref "IC1") (pin "8") (pinfunction "HDEL_8") (pintype "passive"))
      (node (ref "R5") (pin "2") (pinfunction "2_2") (pintype "passive"))
    )
    (net (code "41") (name "Net-(IC1-LDEL)") (class "Default")
      (node (ref "IC1") (pin "9") (pinfunction "LDEL_9") (pintype "passive"))
      (node (ref "R6") (pin "2") (pinfunction "2_2") (pintype "passive"))
    )
    (net (code "42") (name "Net-(IC1-VCC)") (class "Default")
      (node (ref "C1") (pin "2") (pinfunction "2_2") (pintype "passive"))
      (node (ref "C2") (pin "2") (pinfunction "2_2") (pintype "passive"))
      (node (ref "C3") (pin "2") (pinfunction "2_2") (pintype "passive"))
      (node (ref "C4") (pin "2") (pinfunction "2_2") (pintype "passive"))
      (node (ref "IC1") (pin "15") (pinfunction "VCC_15") (pintype "passive"))
      (node (ref "IC1") (pin "16") (pinfunction "VDD_16") (pintype "passive"))
    )
    (net (code "43") (name "Net-(S1-COM)") (class "Default")
      (node (ref "R14") (pin "1") (pinfunction "1_1") (pintype "passive"))
      (node (ref "R15") (pin "1") (pinfunction "1_1") (pintype "passive"))
      (node (ref "S1") (pin "2") (pinfunction "COM_2") (pintype "passive"))
    )
  )
)
